# Step-down.net
KiCad netlist of a schematic drawn in EasyEDA Pro
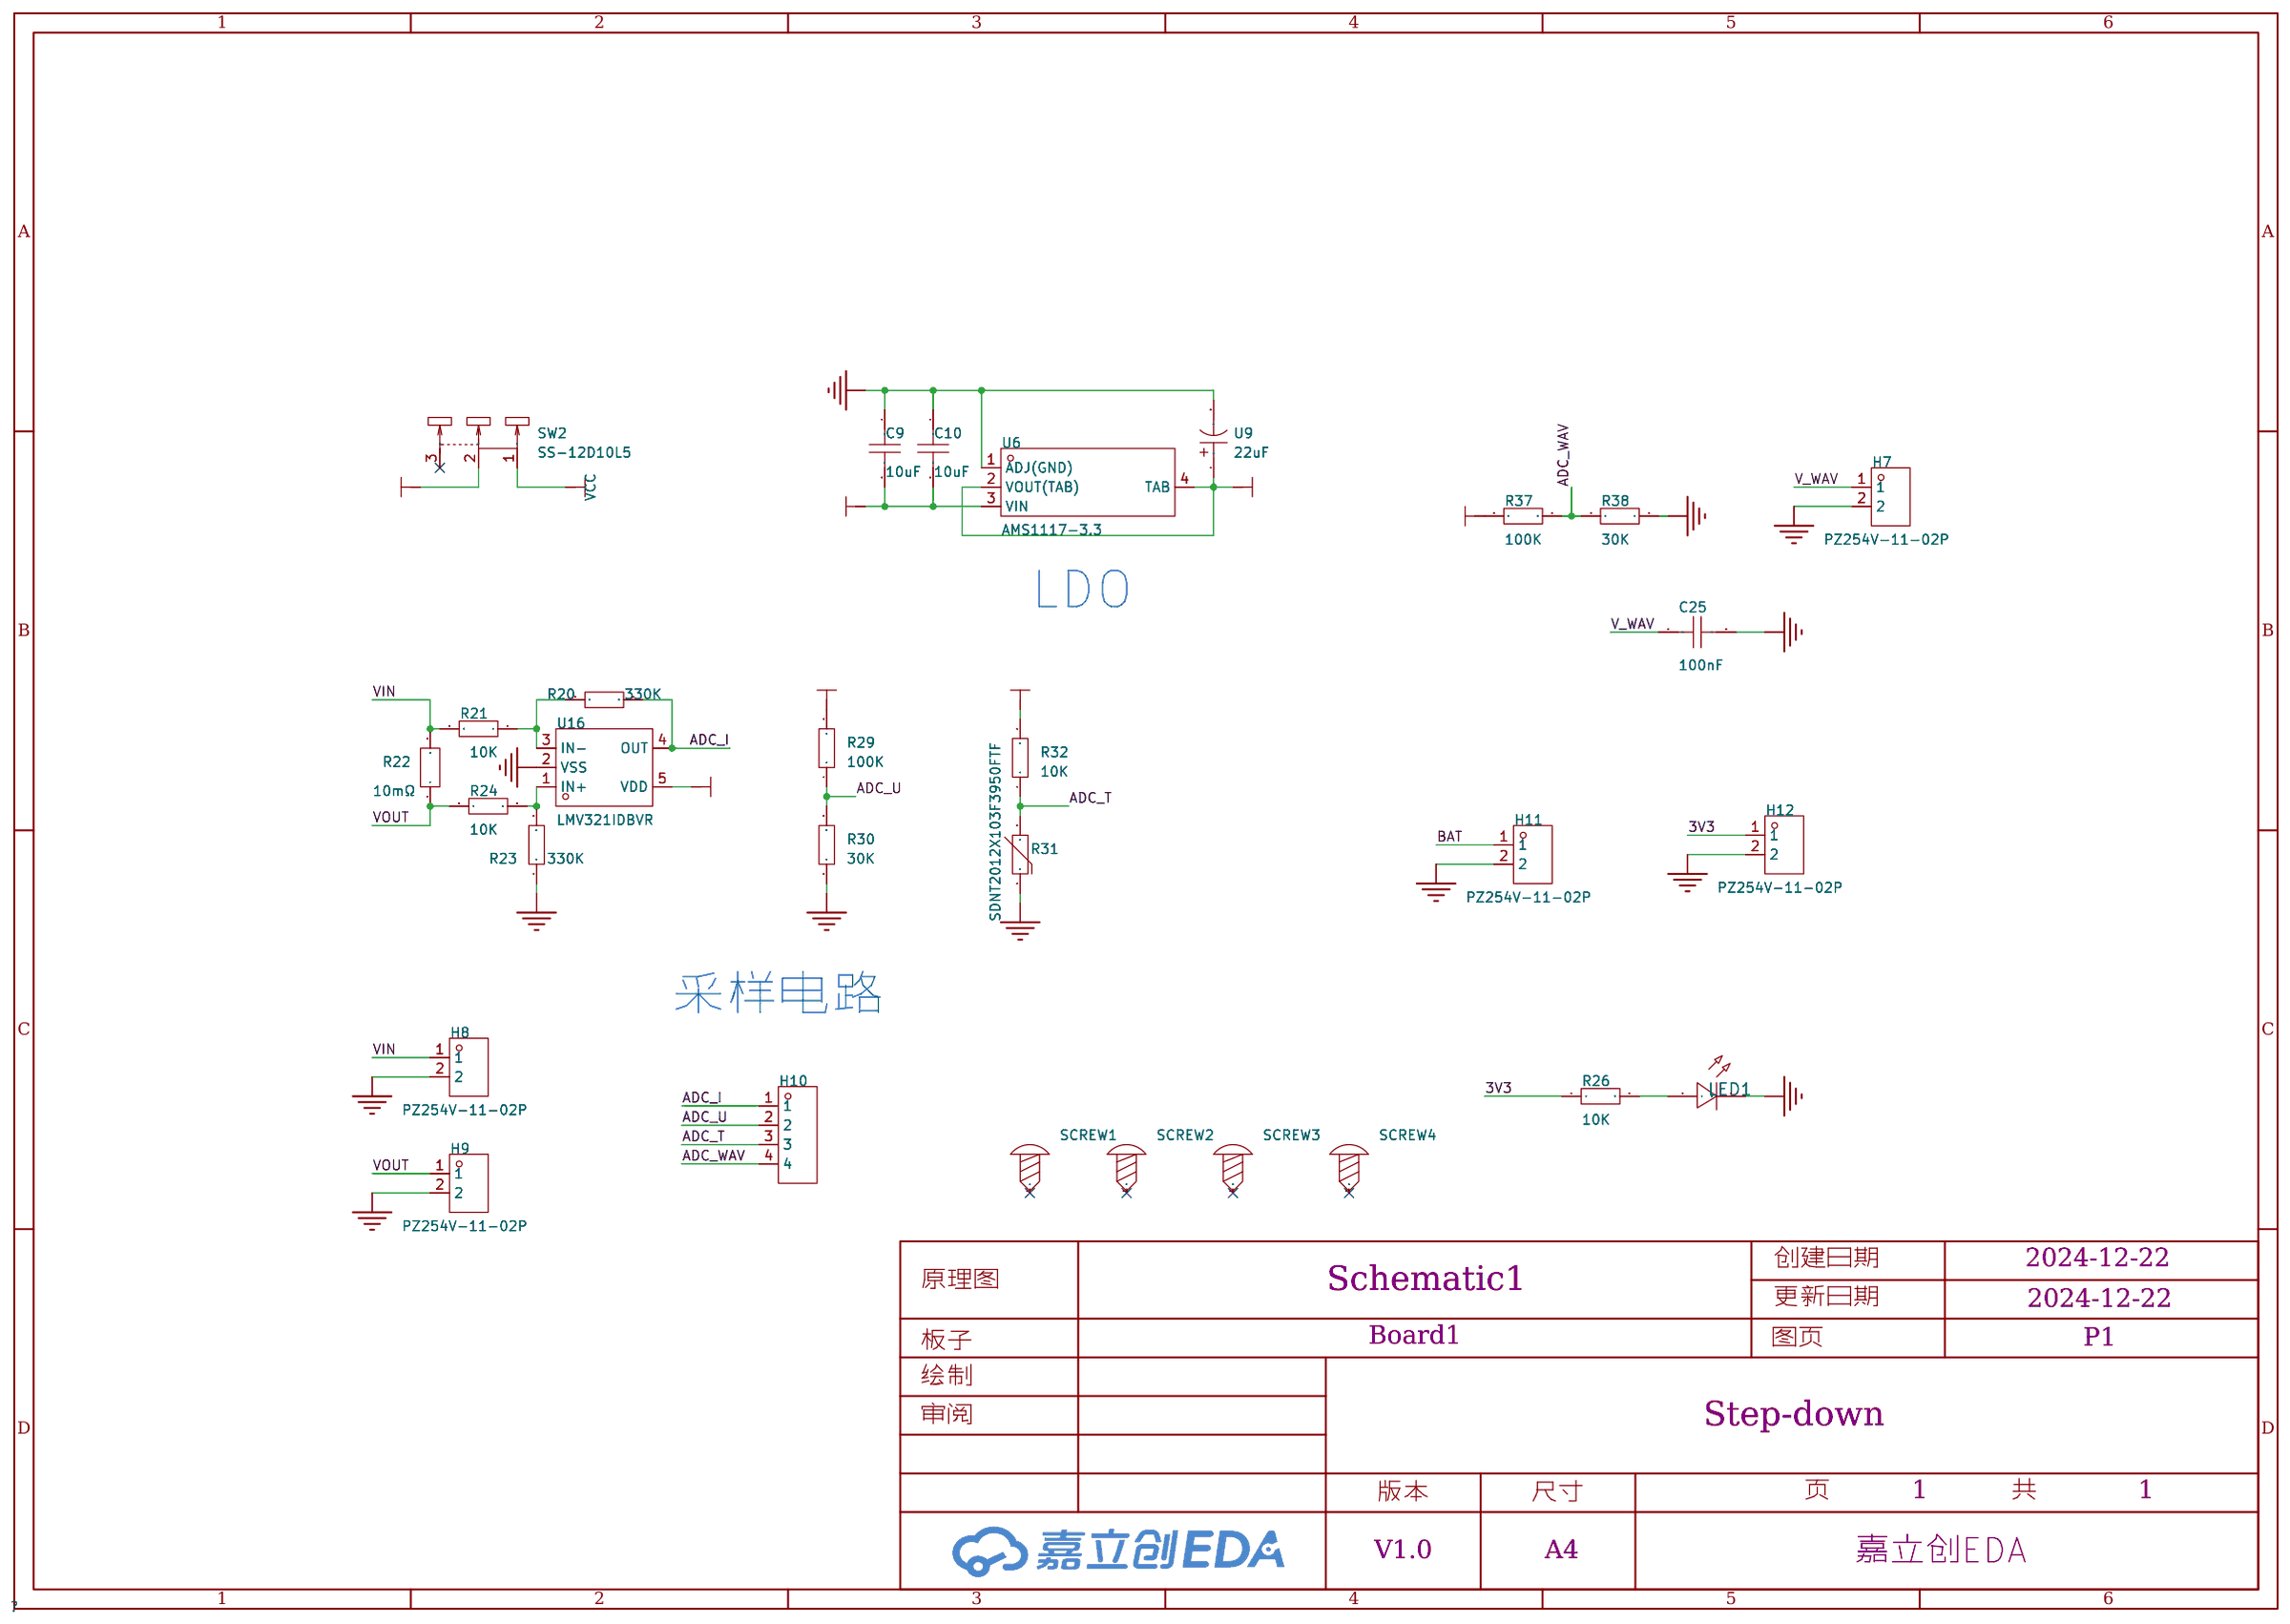
[diagram p0: schematic sheet]

(export (version "E")
  (design (tool "Eeschema 10.0.6"))
  (components
    (comp (ref "C9")
      (value "10uF")
      (footprint "easyedapro:C0603")
      (libsource (lib "easyedapro") (part "CapAcitance"))
    )
    (comp (ref "C10")
      (value "10uF")
      (footprint "easyedapro:C0603")
      (libsource (lib "easyedapro") (part "CapAcitance"))
    )
    (comp (ref "C25")
      (value "100nF")
      (footprint "easyedapro:C0603")
      (libsource (lib "easyedapro") (part "CapAcitance"))
    )
    (comp (ref "H7")
      (value "PZ254V-11-02P")
      (footprint "easyedapro:HDR-TH_2P-P2.54-V-M")
      (fields (field (name "Manufacturer") "XFCN(兴飞)"))
      (libsource (lib "easyedapro") (part "PZ254V-11-02P"))
    )
    (comp (ref "H8")
      (value "PZ254V-11-02P")
      (footprint "easyedapro:HDR-TH_2P-P2.54-V-M")
      (fields (field (name "Manufacturer") "XFCN(兴飞)"))
      (libsource (lib "easyedapro") (part "PZ254V-11-02P"))
    )
    (comp (ref "H9")
      (value "PZ254V-11-02P")
      (footprint "easyedapro:HDR-TH_2P-P2.54-V-M")
      (fields (field (name "Manufacturer") "XFCN(兴飞)"))
      (libsource (lib "easyedapro") (part "PZ254V-11-02P"))
    )
    (comp (ref "H10")
      (value "~")
      (footprint "easyedapro:HDR-TH_4P-P2.54-V-F")
      (libsource (lib "easyedapro") (part "2.54-1*4P母"))
    )
    (comp (ref "H11")
      (value "PZ254V-11-02P")
      (footprint "easyedapro:HDR-TH_2P-P2.54-V-M")
      (fields (field (name "Manufacturer") "XFCN(兴飞)"))
      (libsource (lib "easyedapro") (part "PZ254V-11-02P"))
    )
    (comp (ref "H12")
      (value "PZ254V-11-02P")
      (footprint "easyedapro:HDR-TH_2P-P2.54-V-M")
      (fields (field (name "Manufacturer") "XFCN(兴飞)"))
      (libsource (lib "easyedapro") (part "PZ254V-11-02P"))
    )
    (comp (ref "LED1")
      (value "~")
      (footprint "easyedapro:LED_0603")
      (libsource (lib "easyedapro") (part "LED_R"))
    )
    (comp (ref "R20")
      (value "330K")
      (footprint "easyedapro:R0603")
      (libsource (lib "easyedapro") (part "电阻"))
    )
    (comp (ref "R21") (value "10K") (footprint "easyedapro:R0603") (libsource (lib "easyedapro") (part "电阻")))
    (comp (ref "R22")
      (value "10mΩ")
      (footprint "easyedapro:RES-SMD_L6.4-W3.2-1")
      (description "电阻类型:采样电阻;阻值:5mΩ;精度:±1%;功率:3W;安装方式:贴片;")
      (fields
        (field (name "Manufacturer Part") "HoJLR2512-3W-5mR-1%")
        (field (name "Manufacturer") "Milliohm(毫欧)")
      )
      (libsource (lib "easyedapro") (part "HOJLR2512-3W-5MR-1%"))
    )
    (comp (ref "R23")
      (value "330K")
      (footprint "easyedapro:R0603")
      (libsource (lib "easyedapro") (part "电阻"))
    )
    (comp (ref "R24") (value "10K") (footprint "easyedapro:R0603") (libsource (lib "easyedapro") (part "电阻")))
    (comp (ref "R26") (value "10K") (footprint "easyedapro:R0603") (libsource (lib "easyedapro") (part "电阻")))
    (comp (ref "R29")
      (value "100K")
      (footprint "easyedapro:R0603")
      (libsource (lib "easyedapro") (part "电阻"))
    )
    (comp (ref "R30") (value "30K") (footprint "easyedapro:R0603") (libsource (lib "easyedapro") (part "电阻")))
    (comp (ref "R31")
      (value "SDNT2012X103F3950FTF")
      (footprint "easyedapro:R0805")
      (description "阻值(25°C):10kΩ;B值(25°C/50°C):3950K;电阻精度:±1%;功率:200mW;B值精度:±1%;最大稳态电流(25°C):440uA;")
      (fields (field (name "Manufacturer") "Sunlord(顺络)"))
      (libsource (lib "easyedapro") (part "SDNT2012X103F3950FTF"))
    )
    (comp (ref "R32") (value "10K") (footprint "easyedapro:R0603") (libsource (lib "easyedapro") (part "电阻")))
    (comp (ref "R37")
      (value "100K")
      (footprint "easyedapro:R0603")
      (libsource (lib "easyedapro") (part "电阻"))
    )
    (comp (ref "R38") (value "30K") (footprint "easyedapro:R0603") (libsource (lib "easyedapro") (part "电阻")))
    (comp (ref "SCREW1")
      (value "~")
      (footprint "easyedapro:M2螺丝")
      (libsource (lib "easyedapro") (part "螺丝孔"))
    )
    (comp (ref "SCREW2")
      (value "~")
      (footprint "easyedapro:M2螺丝")
      (libsource (lib "easyedapro") (part "螺丝孔"))
    )
    (comp (ref "SCREW3")
      (value "~")
      (footprint "easyedapro:M2螺丝")
      (libsource (lib "easyedapro") (part "螺丝孔"))
    )
    (comp (ref "SCREW4")
      (value "~")
      (footprint "easyedapro:M2螺丝")
      (libsource (lib "easyedapro") (part "螺丝孔"))
    )
    (comp (ref "SW2")
      (value "SS-12D10L5")
      (footprint "easyedapro:SW-TH_SS-12D10L5")
      (description "电路结构:单刀双掷;安装方式:直插;开关颜色:黑色;额定电流(DC):3A;额定电压(DC):125V;额定电流(AC):3A;额定电压(AC):125V;机械寿命:1万次;")
      (fields (field (name "Manufacturer") "XKB Connectivity(中国星坤)"))
      (libsource (lib "easyedapro") (part "SS-12D10L5"))
    )
    (comp (ref "U6")
      (value "AMS1117-3.3")
      (footprint "easyedapro:SOT-223-4_L6.5-W3.5-P2.30-LS7.0-BR")
      (description "输出类型:固定;最大输入电压:18V;输出电压:3.3V;输出电流:1A;电源纹波抑制比(PSRR):60dB@(120Hz);输出极性:正极;")
      (fields (field (name "Manufacturer") "UMW(友台半导体)"))
      (libsource (lib "easyedapro") (part "AMS1117-3.3_C347222"))
    )
    (comp (ref "U9")
      (value "22uF")
      (footprint "easyedapro:CAP-SMD_L2.0-W1.3-FD")
      (description "容值:22uF;精度:±20%;额定电压:6.3V;等效串联电阻:5.9Ω@100kHz;")
      (fields (field (name "Manufacturer Part") "TMCP0J226MTRF") (field (name "Manufacturer") "VISHAY(威世)"))
      (libsource (lib "easyedapro") (part "TMCP0J226MTRF"))
    )
    (comp (ref "U16")
      (value "LMV321IDBVR")
      (footprint "easyedapro:SOT-23-5_L2.9-W1.6-P0.95-LS2.8-BR")
      (description "低功耗运放")
      (fields (field (name "Manufacturer") "UMW(友台半导体)"))
      (libsource (lib "easyedapro") (part "LMV321IDBVR_C3014306"))
    )
  )
  (nets
    (net (code "1") (name "/ADC_I") (class "Default")
      (node (ref "H10") (pin "1") (pinfunction "1_1") (pintype "unspecified"))
      (node (ref "R20") (pin "1") (pinfunction "1_1") (pintype "input"))
      (node (ref "U16") (pin "4") (pinfunction "OUT_4") (pintype "unspecified"))
    )
    (net (code "2") (name "/ADC_T") (class "Default")
      (node (ref "H10") (pin "3") (pinfunction "3_3") (pintype "unspecified"))
      (node (ref "R31") (pin "2") (pinfunction "2_2") (pintype "input"))
      (node (ref "R32") (pin "1") (pinfunction "1_1") (pintype "input"))
    )
    (net (code "3") (name "/ADC_U") (class "Default")
      (node (ref "H10") (pin "2") (pinfunction "2_2") (pintype "unspecified"))
      (node (ref "R29") (pin "1") (pinfunction "1_1") (pintype "input"))
      (node (ref "R30") (pin "2") (pinfunction "2_2") (pintype "input"))
    )
    (net (code "4") (name "/ADC_WAV") (class "Default")
      (node (ref "H10") (pin "4") (pinfunction "4_4") (pintype "unspecified"))
      (node (ref "R37") (pin "1") (pinfunction "1_1") (pintype "input"))
      (node (ref "R38") (pin "2") (pinfunction "2_2") (pintype "input"))
    )
    (net (code "5") (name "/VOUT") (class "Default")
      (node (ref "H9") (pin "1") (pinfunction "1_1") (pintype "unspecified"))
      (node (ref "R22") (pin "1") (pinfunction "1_1") (pintype "unspecified"))
      (node (ref "R24") (pin "2") (pinfunction "2_2") (pintype "input"))
    )
    (net (code "6") (name "3V3") (class "Default")
      (node (ref "H12") (pin "1") (pinfunction "1_1") (pintype "unspecified"))
      (node (ref "R26") (pin "1") (pinfunction "1_1") (pintype "input"))
      (node (ref "R32") (pin "2") (pinfunction "2_2") (pintype "input"))
      (node (ref "U16") (pin "5") (pinfunction "VDD_5") (pintype "unspecified"))
      (node (ref "U6") (pin "2") (pinfunction "VOUT(TAB)_2") (pintype "unspecified"))
      (node (ref "U6") (pin "4") (pinfunction "TAB_4") (pintype "unspecified"))
      (node (ref "U9") (pin "1") (pinfunction "1_1") (pintype "input"))
    )
    (net (code "7") (name "BAT") (class "Default")
      (node (ref "H11") (pin "1") (pinfunction "1_1") (pintype "unspecified"))
      (node (ref "SW2") (pin "2") (pinfunction "2_2") (pintype "unspecified"))
    )
    (net (code "8") (name "GND") (class "Default")
      (node (ref "C10") (pin "1") (pinfunction "1_1") (pintype "input"))
      (node (ref "C25") (pin "2") (pinfunction "2_2") (pintype "input"))
      (node (ref "C9") (pin "1") (pinfunction "1_1") (pintype "input"))
      (node (ref "H11") (pin "2") (pinfunction "2_2") (pintype "unspecified"))
      (node (ref "H12") (pin "2") (pinfunction "2_2") (pintype "unspecified"))
      (node (ref "H7") (pin "2") (pinfunction "2_2") (pintype "unspecified"))
      (node (ref "H8") (pin "2") (pinfunction "2_2") (pintype "unspecified"))
      (node (ref "H9") (pin "2") (pinfunction "2_2") (pintype "unspecified"))
      (node (ref "LED1") (pin "1") (pinfunction "C_1") (pintype "input"))
      (node (ref "R23") (pin "1") (pinfunction "1_1") (pintype "input"))
      (node (ref "R30") (pin "1") (pinfunction "1_1") (pintype "input"))
      (node (ref "R31") (pin "1") (pinfunction "1_1") (pintype "input"))
      (node (ref "R38") (pin "1") (pinfunction "1_1") (pintype "input"))
      (node (ref "U16") (pin "2") (pinfunction "VSS_2") (pintype "unspecified"))
      (node (ref "U6") (pin "1") (pinfunction "ADJ(GND)_1") (pintype "unspecified"))
      (node (ref "U9") (pin "2") (pinfunction "2_2") (pintype "input"))
    )
    (net (code "9") (name "Net-(LED1-A)") (class "Default")
      (node (ref "LED1") (pin "2") (pinfunction "A_2") (pintype "input"))
      (node (ref "R26") (pin "2") (pinfunction "2_2") (pintype "input"))
    )
    (net (code "10") (name "Net-(U16-IN+)") (class "Default")
      (node (ref "R23") (pin "2") (pinfunction "2_2") (pintype "input"))
      (node (ref "R24") (pin "1") (pinfunction "1_1") (pintype "input"))
      (node (ref "U16") (pin "1") (pinfunction "IN+_1") (pintype "unspecified"))
    )
    (net (code "11") (name "Net-(U16-IN-)") (class "Default")
      (node (ref "R20") (pin "2") (pinfunction "2_2") (pintype "input"))
      (node (ref "R21") (pin "1") (pinfunction "1_1") (pintype "input"))
      (node (ref "U16") (pin "3") (pinfunction "IN-_3") (pintype "unspecified"))
    )
    (net (code "12") (name "VCC") (class "Default")
      (node (ref "C10") (pin "2") (pinfunction "2_2") (pintype "input"))
      (node (ref "C9") (pin "2") (pinfunction "2_2") (pintype "input"))
      (node (ref "SW2") (pin "1") (pinfunction "1_1") (pintype "unspecified"))
      (node (ref "U6") (pin "3") (pinfunction "VIN_3") (pintype "unspecified"))
    )
    (net (code "13") (name "VIN") (class "Default")
      (node (ref "H8") (pin "1") (pinfunction "1_1") (pintype "unspecified"))
      (node (ref "R21") (pin "2") (pinfunction "2_2") (pintype "input"))
      (node (ref "R22") (pin "2") (pinfunction "2_2") (pintype "unspecified"))
      (node (ref "R29") (pin "2") (pinfunction "2_2") (pintype "input"))
    )
    (net (code "14") (name "V_WAV") (class "Default")
      (node (ref "C25") (pin "1") (pinfunction "1_1") (pintype "input"))
      (node (ref "H7") (pin "1") (pinfunction "1_1") (pintype "unspecified"))
      (node (ref "R37") (pin "2") (pinfunction "2_2") (pintype "input"))
    )
    (net (code "15") (name "unconnected-(SCREW1-Pad1)") (class "Default")
      (node (ref "SCREW1") (pin "1") (pinfunction "1_1") (pintype "input+no_connect"))
    )
    (net (code "16") (name "unconnected-(SCREW2-Pad1)") (class "Default")
      (node (ref "SCREW2") (pin "1") (pinfunction "1_1") (pintype "input+no_connect"))
    )
    (net (code "17") (name "unconnected-(SCREW3-Pad1)") (class "Default")
      (node (ref "SCREW3") (pin "1") (pinfunction "1_1") (pintype "input+no_connect"))
    )
    (net (code "18") (name "unconnected-(SCREW4-Pad1)") (class "Default")
      (node (ref "SCREW4") (pin "1") (pinfunction "1_1") (pintype "input+no_connect"))
    )
    (net (code "19") (name "unconnected-(SW2-Pad3)") (class "Default")
      (node (ref "SW2") (pin "3") (pinfunction "3_3") (pintype "unspecified+no_connect"))
    )
  )
)
